# Havoc.net
KiCad netlist of a schematic drawn in EAGLE
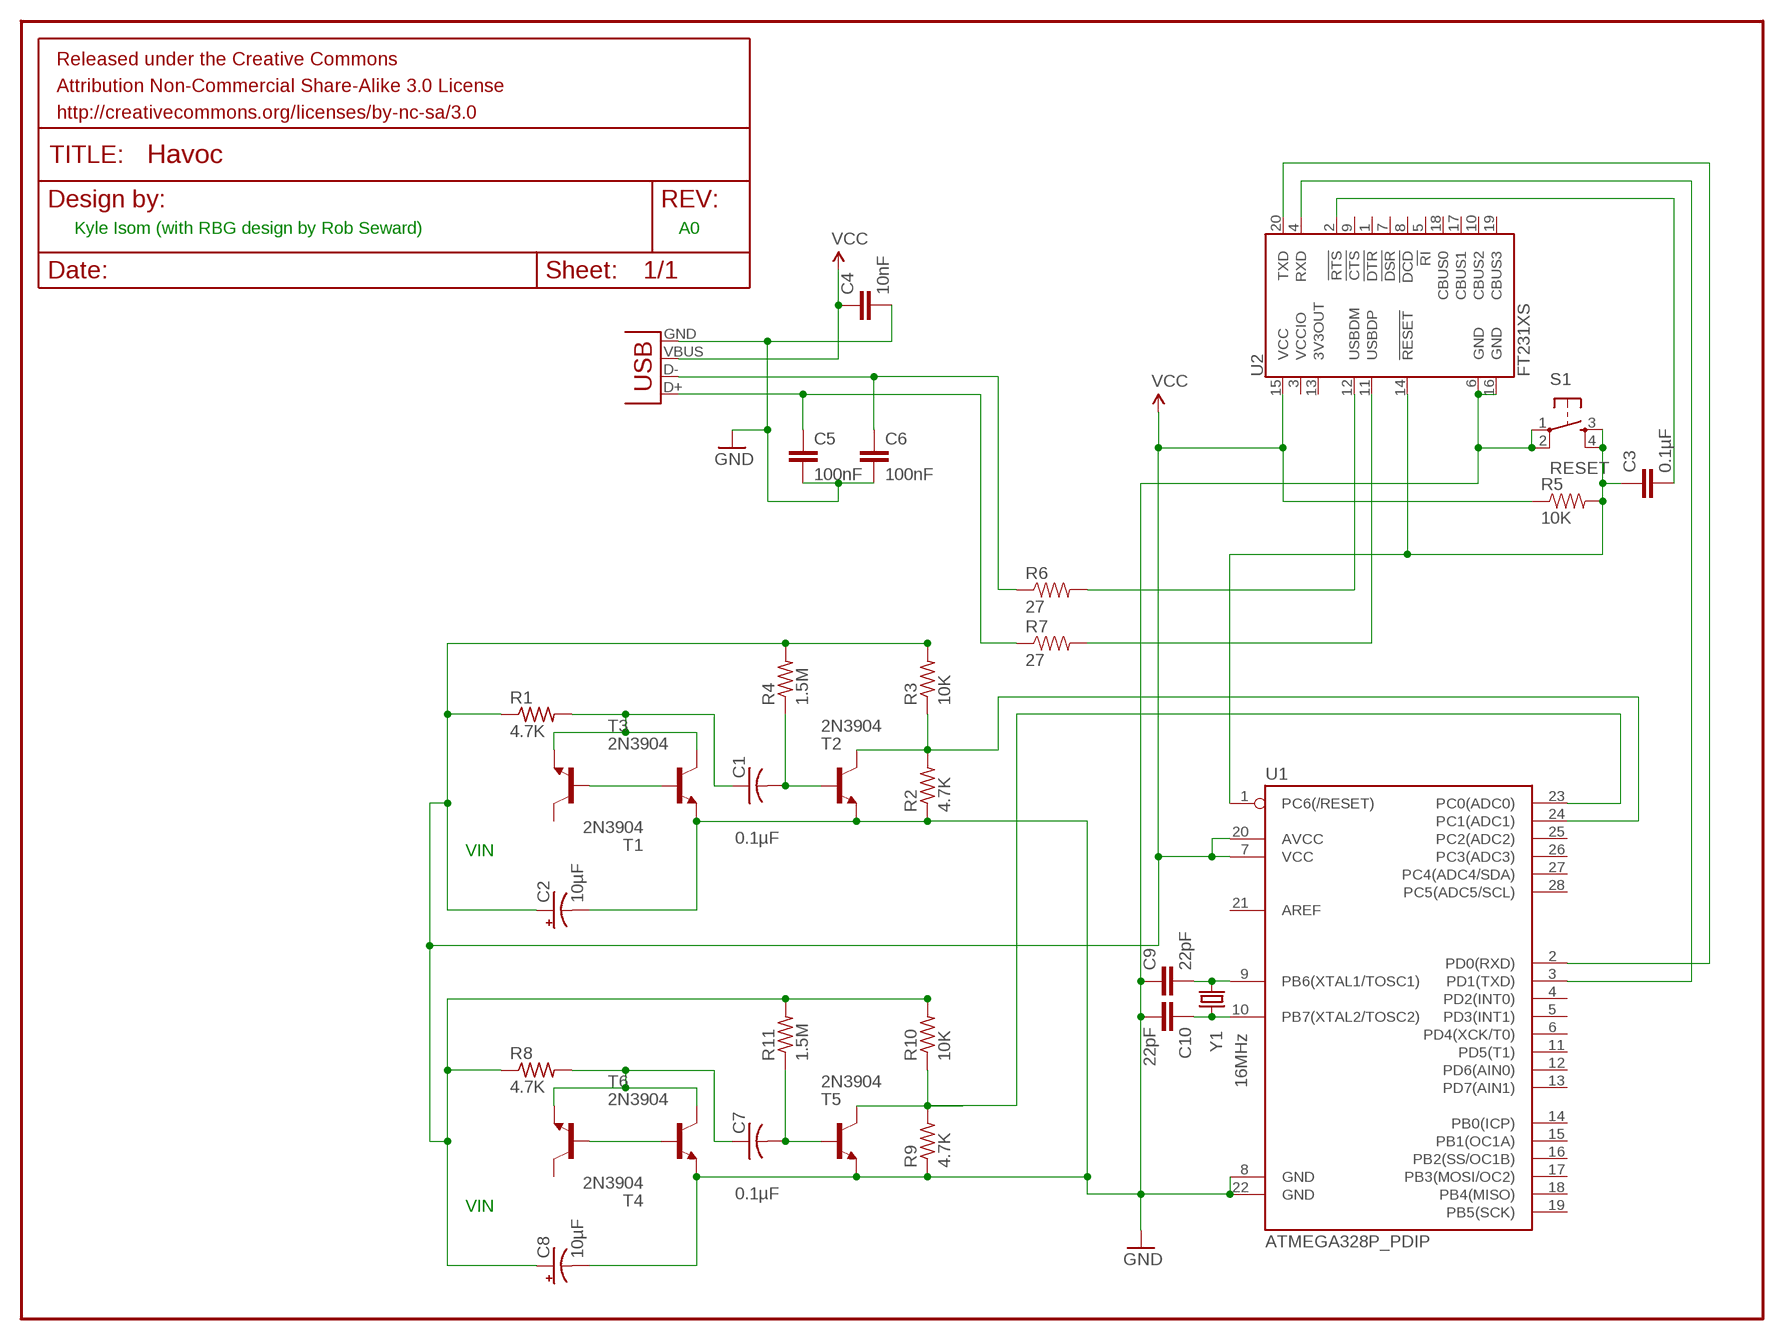
[diagram p0: schematic, sheet 1]

(export (version "E")
  (design (tool "Eeschema 10.0.6"))
  (components
    (comp (ref "C1")
      (value "0.1µF")
      (footprint "eagle-import:C050-030X075")
      (libsource (lib "eagle-import") (part "C-US050-030X075"))
    )
    (comp (ref "C2")
      (value "10µF")
      (footprint "eagle-import:E2-5")
      (libsource (lib "eagle-import") (part "CPOL-USE2-5"))
    )
    (comp (ref "C3")
      (value "0.1µF")
      (footprint "eagle-import:CAP-PTH-SMALL")
      (libsource (lib "eagle-import") (part "SparkFun-Passives_CAPPTH"))
    )
    (comp (ref "C4")
      (value "10nF")
      (footprint "eagle-import:CAP-PTH-SMALL")
      (libsource (lib "eagle-import") (part "SparkFun-Passives_CAPPTH"))
    )
    (comp (ref "C5")
      (value "100nF")
      (footprint "eagle-import:CAP-PTH-SMALL")
      (libsource (lib "eagle-import") (part "CAPPTH"))
    )
    (comp (ref "C6")
      (value "100nF")
      (footprint "eagle-import:CAP-PTH-SMALL")
      (libsource (lib "eagle-import") (part "CAPPTH"))
    )
    (comp (ref "C7")
      (value "0.1µF")
      (footprint "eagle-import:C050-030X075")
      (libsource (lib "eagle-import") (part "C-US050-030X075"))
    )
    (comp (ref "C8")
      (value "10µF")
      (footprint "eagle-import:E2-5")
      (libsource (lib "eagle-import") (part "CPOL-USE2-5"))
    )
    (comp (ref "C9")
      (value "22pF")
      (footprint "eagle-import:CAP-PTH-SMALL")
      (libsource (lib "eagle-import") (part "CAPPTH"))
    )
    (comp (ref "C10")
      (value "22pF")
      (footprint "eagle-import:CAP-PTH-SMALL")
      (libsource (lib "eagle-import") (part "CAPPTH"))
    )
    (comp (ref "FRAME1")
      (value "FRAME-LETTER")
      (footprint "eagle-import:CREATIVE_COMMONS")
      (libsource (lib "eagle-import") (part "FRAME-LETTER"))
    )
    (comp (ref "JP1")
      (value "USBSMD")
      (footprint "eagle-import:USB-MINIB")
      (libsource (lib "eagle-import") (part "USBSMD"))
    )
    (comp (ref "R1")
      (value "4.7K")
      (footprint "eagle-import:0207_7")
      (libsource (lib "eagle-import") (part "R-US_0207/7"))
    )
    (comp (ref "R2")
      (value "4.7K")
      (footprint "eagle-import:0207_7")
      (libsource (lib "eagle-import") (part "R-US_0207/7"))
    )
    (comp (ref "R3")
      (value "10K")
      (footprint "eagle-import:0207_7")
      (libsource (lib "eagle-import") (part "R-US_0207/7"))
    )
    (comp (ref "R4")
      (value "1.5M")
      (footprint "eagle-import:0207_7")
      (libsource (lib "eagle-import") (part "R-US_0207/7"))
    )
    (comp (ref "R5")
      (value "10K")
      (footprint "eagle-import:AXIAL-0.6")
      (libsource (lib "eagle-import") (part "RESISTORPTH-1W"))
    )
    (comp (ref "R6")
      (value "27")
      (footprint "eagle-import:AXIAL-0.6")
      (libsource (lib "eagle-import") (part "RESISTORPTH-1W"))
    )
    (comp (ref "R7")
      (value "27")
      (footprint "eagle-import:AXIAL-0.6")
      (libsource (lib "eagle-import") (part "RESISTORPTH-1W"))
    )
    (comp (ref "R8")
      (value "4.7K")
      (footprint "eagle-import:0207_7")
      (libsource (lib "eagle-import") (part "R-US_0207/7"))
    )
    (comp (ref "R9")
      (value "4.7K")
      (footprint "eagle-import:0207_7")
      (libsource (lib "eagle-import") (part "R-US_0207/7"))
    )
    (comp (ref "R10")
      (value "10K")
      (footprint "eagle-import:0207_7")
      (libsource (lib "eagle-import") (part "R-US_0207/7"))
    )
    (comp (ref "R11")
      (value "1.5M")
      (footprint "eagle-import:0207_7")
      (libsource (lib "eagle-import") (part "R-US_0207/7"))
    )
    (comp (ref "S1")
      (value "RESET")
      (footprint "eagle-import:TACTILE-PTH")
      (libsource (lib "eagle-import") (part "TAC_SWITCHPTH"))
    )
    (comp (ref "T1")
      (value "2N3904")
      (footprint "eagle-import:TO92")
      (libsource (lib "eagle-import") (part "2N3904"))
    )
    (comp (ref "T2")
      (value "2N3904")
      (footprint "eagle-import:TO92")
      (libsource (lib "eagle-import") (part "2N3904"))
    )
    (comp (ref "T3")
      (value "2N3904")
      (footprint "eagle-import:TO92")
      (libsource (lib "eagle-import") (part "2N3904"))
    )
    (comp (ref "T4")
      (value "2N3904")
      (footprint "eagle-import:TO92")
      (libsource (lib "eagle-import") (part "2N3904"))
    )
    (comp (ref "T5")
      (value "2N3904")
      (footprint "eagle-import:TO92")
      (libsource (lib "eagle-import") (part "2N3904"))
    )
    (comp (ref "T6")
      (value "2N3904")
      (footprint "eagle-import:TO92")
      (libsource (lib "eagle-import") (part "2N3904"))
    )
    (comp (ref "U1")
      (value "ATMEGA328P_PDIP")
      (footprint "eagle-import:DIL28-3")
      (libsource (lib "eagle-import") (part "ATMEGA328P_PDIP"))
    )
    (comp (ref "U2")
      (value "FT231XS")
      (footprint "eagle-import:SSOP20_L")
      (libsource (lib "eagle-import") (part "FT231XS"))
    )
    (comp (ref "Y1")
      (value "16MHz")
      (footprint "eagle-import:HC49US")
      (libsource (lib "eagle-import") (part "CRYSTALHC49US"))
    )
  )
  (nets
    (net (code "1") (name "GND") (class "Default")
      (node (ref "C10") (pin "2") (pinfunction "2_2") (pintype "passive"))
      (node (ref "C2") (pin "-") (pinfunction "-_-") (pintype "passive"))
      (node (ref "C4") (pin "2") (pinfunction "2_2") (pintype "passive"))
      (node (ref "C5") (pin "2") (pinfunction "2_2") (pintype "passive"))
      (node (ref "C6") (pin "2") (pinfunction "2_2") (pintype "passive"))
      (node (ref "C8") (pin "-") (pinfunction "-_-") (pintype "passive"))
      (node (ref "C9") (pin "1") (pinfunction "1_1") (pintype "passive"))
      (node (ref "JP1") (pin "GND") (pinfunction "GND_GND") (pintype "bidirectional"))
      (node (ref "R2") (pin "1") (pinfunction "1_1") (pintype "passive"))
      (node (ref "R9") (pin "1") (pinfunction "1_1") (pintype "passive"))
      (node (ref "S1") (pin "1") (pinfunction "1_1") (pintype "passive"))
      (node (ref "S1") (pin "2") (pinfunction "2_2") (pintype "passive"))
      (node (ref "T2") (pin "3") (pinfunction "E_3") (pintype "passive"))
      (node (ref "T3") (pin "3") (pinfunction "E_3") (pintype "passive"))
      (node (ref "T5") (pin "3") (pinfunction "E_3") (pintype "passive"))
      (node (ref "T6") (pin "3") (pinfunction "E_3") (pintype "passive"))
      (node (ref "U1") (pin "22") (pinfunction "GND_22") (pintype "bidirectional"))
      (node (ref "U1") (pin "8") (pinfunction "GND_8") (pintype "bidirectional"))
      (node (ref "U2") (pin "16") (pinfunction "GND_16") (pintype "bidirectional"))
      (node (ref "U2") (pin "6") (pinfunction "GND_6") (pintype "bidirectional"))
    )
    (net (code "2") (name "Net-(R5-2)") (class "Default")
      (node (ref "C3") (pin "1") (pinfunction "1_1") (pintype "passive"))
      (node (ref "R5") (pin "P$2") (pinfunction "2_P$2") (pintype "passive"))
      (node (ref "S1") (pin "3") (pinfunction "3_3") (pintype "passive"))
      (node (ref "S1") (pin "4") (pinfunction "4_4") (pintype "passive"))
      (node (ref "U1") (pin "1") (pinfunction "PC6(/RESET)_1") (pintype "bidirectional"))
      (node (ref "U2") (pin "14") (pinfunction "~{RESET}_14") (pintype "bidirectional"))
    )
    (net (code "3") (name "Net-(R6-1)") (class "Default")
      (node (ref "C6") (pin "1") (pinfunction "1_1") (pintype "passive"))
      (node (ref "JP1") (pin "D-") (pinfunction "D-_D-") (pintype "bidirectional"))
      (node (ref "R6") (pin "P$1") (pinfunction "1_P$1") (pintype "passive"))
    )
    (net (code "4") (name "Net-(R6-2)") (class "Default")
      (node (ref "R6") (pin "P$2") (pinfunction "2_P$2") (pintype "passive"))
      (node (ref "U2") (pin "12") (pinfunction "USBDM_12") (pintype "bidirectional"))
    )
    (net (code "5") (name "Net-(R7-1)") (class "Default")
      (node (ref "C5") (pin "1") (pinfunction "1_1") (pintype "passive"))
      (node (ref "JP1") (pin "D+") (pinfunction "D+_D+") (pintype "bidirectional"))
      (node (ref "R7") (pin "P$1") (pinfunction "1_P$1") (pintype "passive"))
    )
    (net (code "6") (name "Net-(R7-2)") (class "Default")
      (node (ref "R7") (pin "P$2") (pinfunction "2_P$2") (pintype "passive"))
      (node (ref "U2") (pin "11") (pinfunction "USBDP_11") (pintype "bidirectional"))
    )
    (net (code "7") (name "Net-(T1-B)") (class "Default")
      (node (ref "T1") (pin "2") (pinfunction "B_2") (pintype "passive"))
      (node (ref "T3") (pin "2") (pinfunction "B_2") (pintype "passive"))
    )
    (net (code "8") (name "Net-(T1-E)") (class "Default")
      (node (ref "C1") (pin "1") (pinfunction "1_1") (pintype "passive"))
      (node (ref "R1") (pin "2") (pinfunction "2_2") (pintype "passive"))
      (node (ref "T1") (pin "3") (pinfunction "E_3") (pintype "passive"))
      (node (ref "T3") (pin "1") (pinfunction "C_1") (pintype "passive"))
    )
    (net (code "9") (name "Net-(T2-B)") (class "Default")
      (node (ref "C1") (pin "2") (pinfunction "2_2") (pintype "passive"))
      (node (ref "R4") (pin "1") (pinfunction "1_1") (pintype "passive"))
      (node (ref "T2") (pin "2") (pinfunction "B_2") (pintype "passive"))
    )
    (net (code "10") (name "Net-(T2-C)") (class "Default")
      (node (ref "R2") (pin "2") (pinfunction "2_2") (pintype "passive"))
      (node (ref "R3") (pin "1") (pinfunction "1_1") (pintype "passive"))
      (node (ref "T2") (pin "1") (pinfunction "C_1") (pintype "passive"))
      (node (ref "U1") (pin "24") (pinfunction "PC1(ADC1)_24") (pintype "bidirectional"))
    )
    (net (code "11") (name "Net-(T4-B)") (class "Default")
      (node (ref "T4") (pin "2") (pinfunction "B_2") (pintype "passive"))
      (node (ref "T6") (pin "2") (pinfunction "B_2") (pintype "passive"))
    )
    (net (code "12") (name "Net-(T4-E)") (class "Default")
      (node (ref "C7") (pin "1") (pinfunction "1_1") (pintype "passive"))
      (node (ref "R8") (pin "2") (pinfunction "2_2") (pintype "passive"))
      (node (ref "T4") (pin "3") (pinfunction "E_3") (pintype "passive"))
      (node (ref "T6") (pin "1") (pinfunction "C_1") (pintype "passive"))
    )
    (net (code "13") (name "Net-(T5-B)") (class "Default")
      (node (ref "C7") (pin "2") (pinfunction "2_2") (pintype "passive"))
      (node (ref "R11") (pin "1") (pinfunction "1_1") (pintype "passive"))
      (node (ref "T5") (pin "2") (pinfunction "B_2") (pintype "passive"))
    )
    (net (code "14") (name "Net-(T5-C)") (class "Default")
      (node (ref "R10") (pin "1") (pinfunction "1_1") (pintype "passive"))
      (node (ref "R9") (pin "2") (pinfunction "2_2") (pintype "passive"))
      (node (ref "T5") (pin "1") (pinfunction "C_1") (pintype "passive"))
      (node (ref "U1") (pin "23") (pinfunction "PC0(ADC0)_23") (pintype "bidirectional"))
    )
    (net (code "15") (name "Net-(U1-PB6(XTAL1{slash}TOSC1))") (class "Default")
      (node (ref "C9") (pin "2") (pinfunction "2_2") (pintype "passive"))
      (node (ref "U1") (pin "9") (pinfunction "PB6(XTAL1/TOSC1)_9") (pintype "bidirectional"))
      (node (ref "Y1") (pin "2") (pinfunction "2_2") (pintype "passive"))
    )
    (net (code "16") (name "Net-(U1-PB7(XTAL2{slash}TOSC2))") (class "Default")
      (node (ref "C10") (pin "1") (pinfunction "1_1") (pintype "passive"))
      (node (ref "U1") (pin "10") (pinfunction "PB7(XTAL2/TOSC2)_10") (pintype "bidirectional"))
      (node (ref "Y1") (pin "1") (pinfunction "1_1") (pintype "passive"))
    )
    (net (code "17") (name "Net-(U1-PD0(RXD))") (class "Default")
      (node (ref "U1") (pin "2") (pinfunction "PD0(RXD)_2") (pintype "bidirectional"))
      (node (ref "U2") (pin "20") (pinfunction "TXD_20") (pintype "bidirectional"))
    )
    (net (code "18") (name "Net-(U1-PD1(TXD))") (class "Default")
      (node (ref "U1") (pin "3") (pinfunction "PD1(TXD)_3") (pintype "bidirectional"))
      (node (ref "U2") (pin "4") (pinfunction "RXD_4") (pintype "bidirectional"))
    )
    (net (code "19") (name "Net-(U2-~{RTS})") (class "Default")
      (node (ref "C3") (pin "2") (pinfunction "2_2") (pintype "passive"))
      (node (ref "U2") (pin "2") (pinfunction "~{RTS}_2") (pintype "bidirectional"))
    )
    (net (code "20") (name "VCC") (class "Default")
      (node (ref "C2") (pin "+") (pinfunction "+_+") (pintype "passive"))
      (node (ref "C4") (pin "1") (pinfunction "1_1") (pintype "passive"))
      (node (ref "C8") (pin "+") (pinfunction "+_+") (pintype "passive"))
      (node (ref "JP1") (pin "VBUS") (pinfunction "VBUS_VBUS") (pintype "bidirectional"))
      (node (ref "R1") (pin "1") (pinfunction "1_1") (pintype "passive"))
      (node (ref "R10") (pin "2") (pinfunction "2_2") (pintype "passive"))
      (node (ref "R11") (pin "2") (pinfunction "2_2") (pintype "passive"))
      (node (ref "R3") (pin "2") (pinfunction "2_2") (pintype "passive"))
      (node (ref "R4") (pin "2") (pinfunction "2_2") (pintype "passive"))
      (node (ref "R5") (pin "P$1") (pinfunction "1_P$1") (pintype "passive"))
      (node (ref "R8") (pin "1") (pinfunction "1_1") (pintype "passive"))
      (node (ref "U1") (pin "20") (pinfunction "AVCC_20") (pintype "bidirectional"))
      (node (ref "U1") (pin "7") (pinfunction "VCC_7") (pintype "bidirectional"))
      (node (ref "U2") (pin "15") (pinfunction "VCC_15") (pintype "bidirectional"))
    )
    (net (code "21") (name "unconnected-(T1-C-Pad1)") (class "Default")
      (node (ref "T1") (pin "1") (pinfunction "C_1") (pintype "passive"))
    )
    (net (code "22") (name "unconnected-(T4-C-Pad1)") (class "Default")
      (node (ref "T4") (pin "1") (pinfunction "C_1") (pintype "passive"))
    )
    (net (code "23") (name "unconnected-(U1-AREF-Pad21)") (class "Default")
      (node (ref "U1") (pin "21") (pinfunction "AREF_21") (pintype "bidirectional"))
    )
    (net (code "24") (name "unconnected-(U1-PB0(ICP)-Pad14)") (class "Default")
      (node (ref "U1") (pin "14") (pinfunction "PB0(ICP)_14") (pintype "bidirectional"))
    )
    (net (code "25") (name "unconnected-(U1-PB1(OC1A)-Pad15)") (class "Default")
      (node (ref "U1") (pin "15") (pinfunction "PB1(OC1A)_15") (pintype "bidirectional"))
    )
    (net (code "26") (name "unconnected-(U1-PB2(SS{slash}OC1B)-Pad16)") (class "Default")
      (node (ref "U1") (pin "16") (pinfunction "PB2(SS/OC1B)_16") (pintype "bidirectional"))
    )
    (net (code "27") (name "unconnected-(U1-PB3(MOSI{slash}OC2)-Pad17)") (class "Default")
      (node (ref "U1") (pin "17") (pinfunction "PB3(MOSI/OC2)_17") (pintype "bidirectional"))
    )
    (net (code "28") (name "unconnected-(U1-PB4(MISO)-Pad18)") (class "Default")
      (node (ref "U1") (pin "18") (pinfunction "PB4(MISO)_18") (pintype "bidirectional"))
    )
    (net (code "29") (name "unconnected-(U1-PB5(SCK)-Pad19)") (class "Default")
      (node (ref "U1") (pin "19") (pinfunction "PB5(SCK)_19") (pintype "bidirectional"))
    )
    (net (code "30") (name "unconnected-(U1-PC2(ADC2)-Pad25)") (class "Default")
      (node (ref "U1") (pin "25") (pinfunction "PC2(ADC2)_25") (pintype "bidirectional"))
    )
    (net (code "31") (name "unconnected-(U1-PC3(ADC3)-Pad26)") (class "Default")
      (node (ref "U1") (pin "26") (pinfunction "PC3(ADC3)_26") (pintype "bidirectional"))
    )
    (net (code "32") (name "unconnected-(U1-PC4(ADC4{slash}SDA)-Pad27)") (class "Default")
      (node (ref "U1") (pin "27") (pinfunction "PC4(ADC4/SDA)_27") (pintype "bidirectional"))
    )
    (net (code "33") (name "unconnected-(U1-PC5(ADC5{slash}SCL)-Pad28)") (class "Default")
      (node (ref "U1") (pin "28") (pinfunction "PC5(ADC5/SCL)_28") (pintype "bidirectional"))
    )
    (net (code "34") (name "unconnected-(U1-PD2(INT0)-Pad4)") (class "Default")
      (node (ref "U1") (pin "4") (pinfunction "PD2(INT0)_4") (pintype "bidirectional"))
    )
    (net (code "35") (name "unconnected-(U1-PD3(INT1)-Pad5)") (class "Default")
      (node (ref "U1") (pin "5") (pinfunction "PD3(INT1)_5") (pintype "bidirectional"))
    )
    (net (code "36") (name "unconnected-(U1-PD4(XCK{slash}T0)-Pad6)") (class "Default")
      (node (ref "U1") (pin "6") (pinfunction "PD4(XCK/T0)_6") (pintype "bidirectional"))
    )
    (net (code "37") (name "unconnected-(U1-PD5(T1)-Pad11)") (class "Default")
      (node (ref "U1") (pin "11") (pinfunction "PD5(T1)_11") (pintype "bidirectional"))
    )
    (net (code "38") (name "unconnected-(U1-PD6(AIN0)-Pad12)") (class "Default")
      (node (ref "U1") (pin "12") (pinfunction "PD6(AIN0)_12") (pintype "bidirectional"))
    )
    (net (code "39") (name "unconnected-(U1-PD7(AIN1)-Pad13)") (class "Default")
      (node (ref "U1") (pin "13") (pinfunction "PD7(AIN1)_13") (pintype "bidirectional"))
    )
    (net (code "40") (name "unconnected-(U2-3V3OUT-Pad13)") (class "Default")
      (node (ref "U2") (pin "13") (pinfunction "3V3OUT_13") (pintype "bidirectional"))
    )
    (net (code "41") (name "unconnected-(U2-CBUS0-Pad18)") (class "Default")
      (node (ref "U2") (pin "18") (pinfunction "CBUS0_18") (pintype "bidirectional"))
    )
    (net (code "42") (name "unconnected-(U2-CBUS1-Pad17)") (class "Default")
      (node (ref "U2") (pin "17") (pinfunction "CBUS1_17") (pintype "bidirectional"))
    )
    (net (code "43") (name "unconnected-(U2-CBUS2-Pad10)") (class "Default")
      (node (ref "U2") (pin "10") (pinfunction "CBUS2_10") (pintype "bidirectional"))
    )
    (net (code "44") (name "unconnected-(U2-CBUS3-Pad19)") (class "Default")
      (node (ref "U2") (pin "19") (pinfunction "CBUS3_19") (pintype "bidirectional"))
    )
    (net (code "45") (name "unconnected-(U2-VCCIO-Pad3)") (class "Default")
      (node (ref "U2") (pin "3") (pinfunction "VCCIO_3") (pintype "bidirectional"))
    )
    (net (code "46") (name "unconnected-(U2-~{CTS}-Pad9)") (class "Default")
      (node (ref "U2") (pin "9") (pinfunction "~{CTS}_9") (pintype "bidirectional"))
    )
    (net (code "47") (name "unconnected-(U2-~{DCD}-Pad8)") (class "Default")
      (node (ref "U2") (pin "8") (pinfunction "~{DCD}_8") (pintype "bidirectional"))
    )
    (net (code "48") (name "unconnected-(U2-~{DSR}-Pad7)") (class "Default")
      (node (ref "U2") (pin "7") (pinfunction "~{DSR}_7") (pintype "bidirectional"))
    )
    (net (code "49") (name "unconnected-(U2-~{DTR}-Pad1)") (class "Default")
      (node (ref "U2") (pin "1") (pinfunction "~{DTR}_1") (pintype "bidirectional"))
    )
    (net (code "50") (name "unconnected-(U2-~{RI}-Pad5)") (class "Default")
      (node (ref "U2") (pin "5") (pinfunction "~{RI}_5") (pintype "bidirectional"))
    )
  )
)
